# LCR.net
KiCad netlist of a schematic drawn in EAGLE
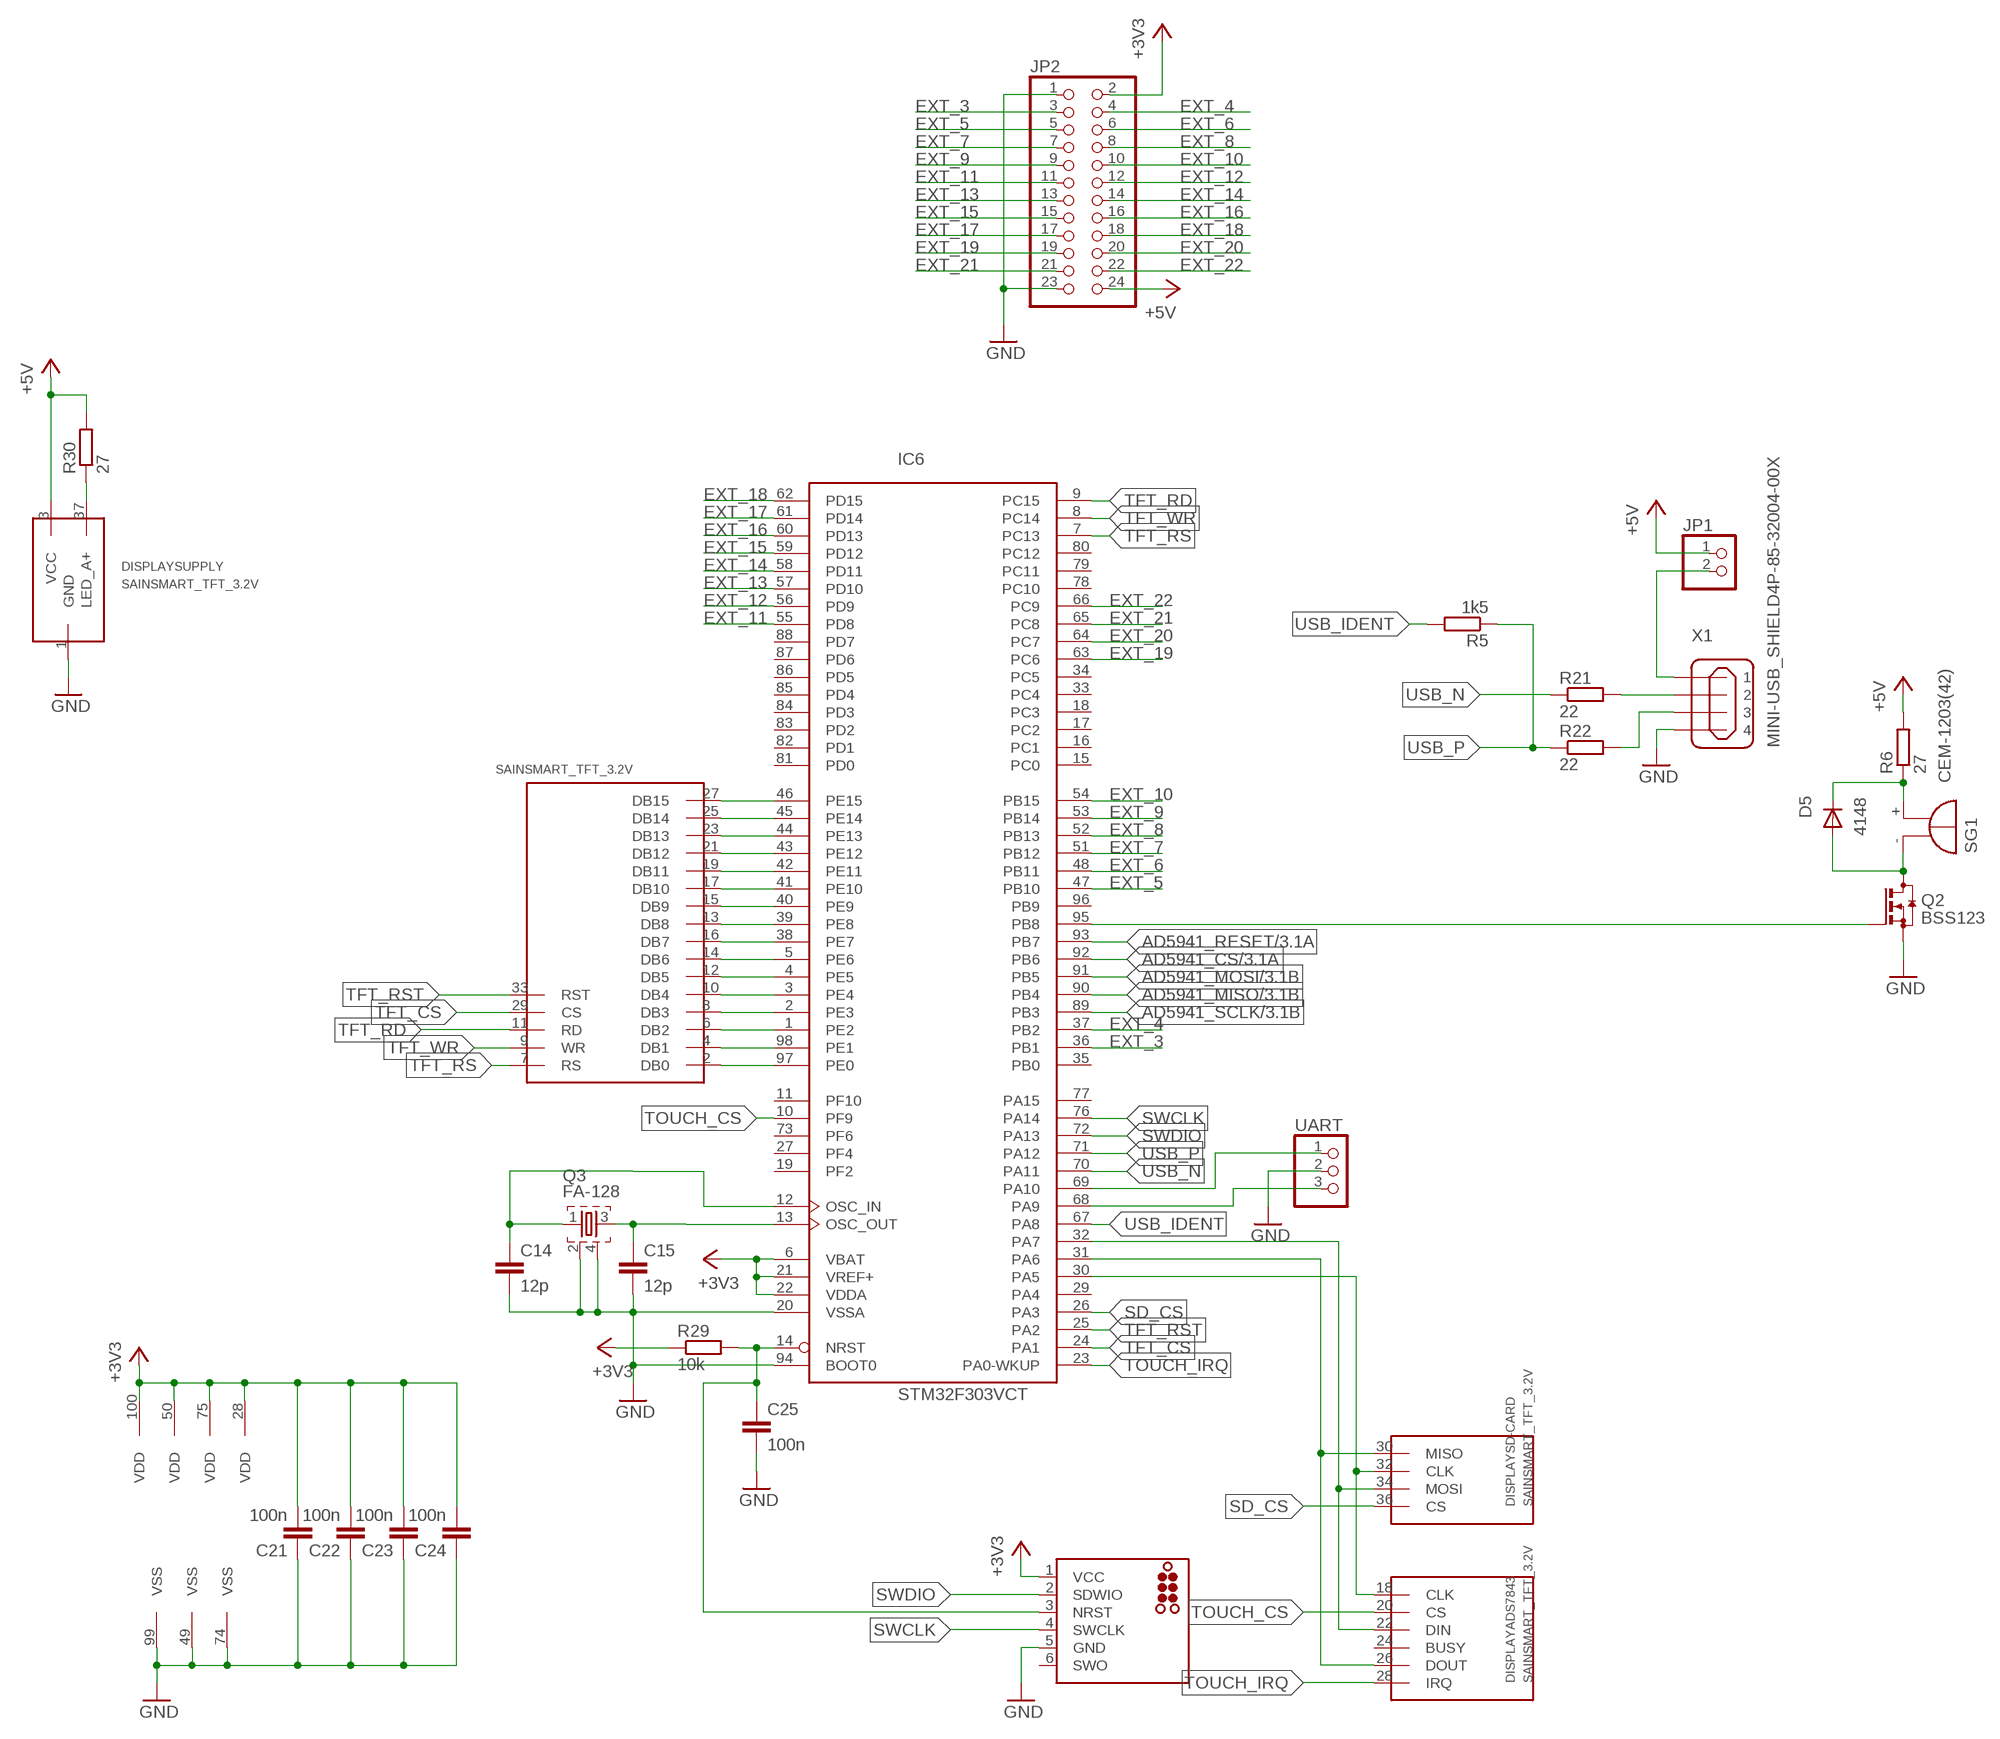
[diagram p0: schematic, sheet 1]
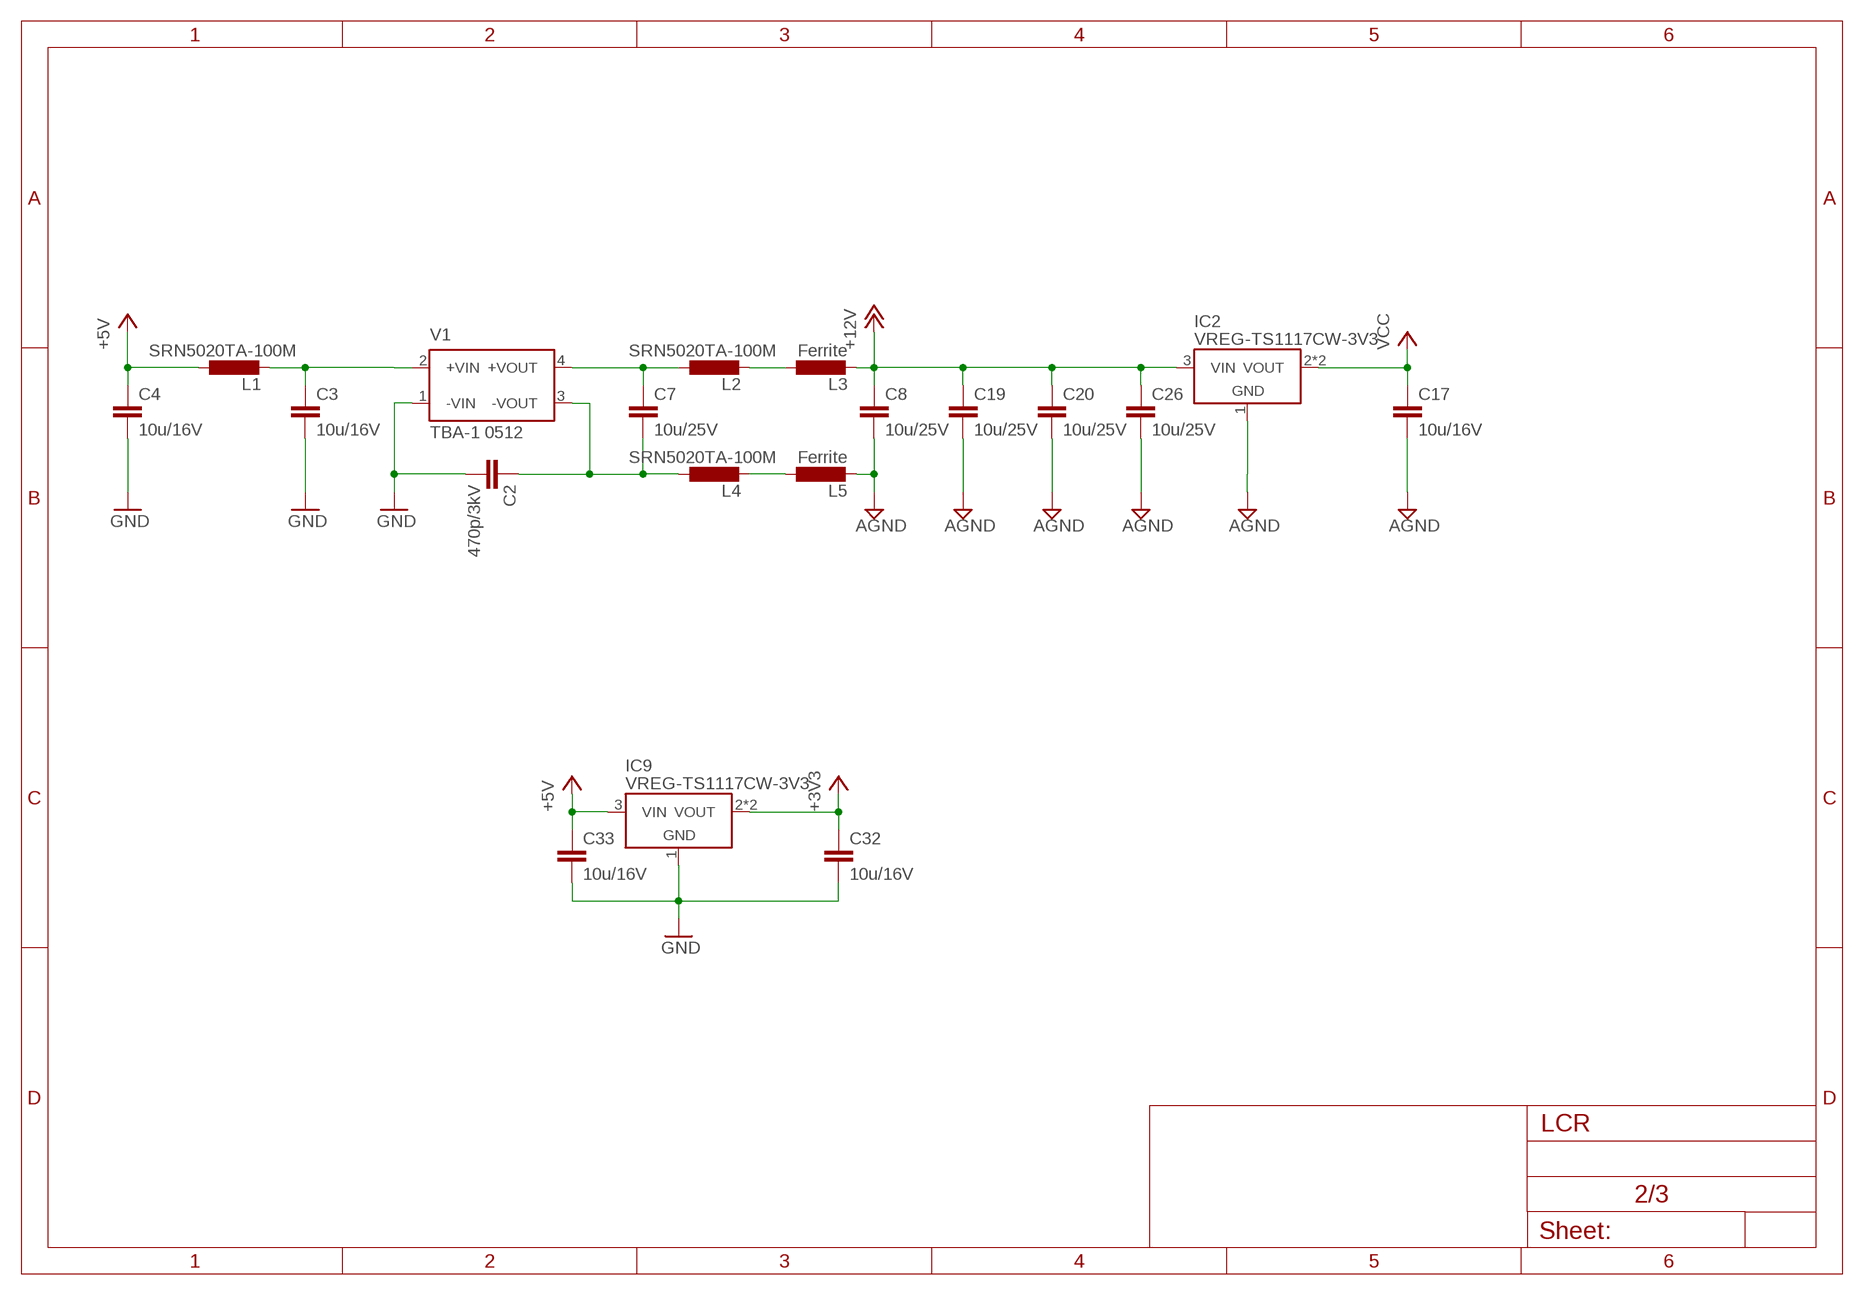
[diagram p1: schematic, sheet 2]
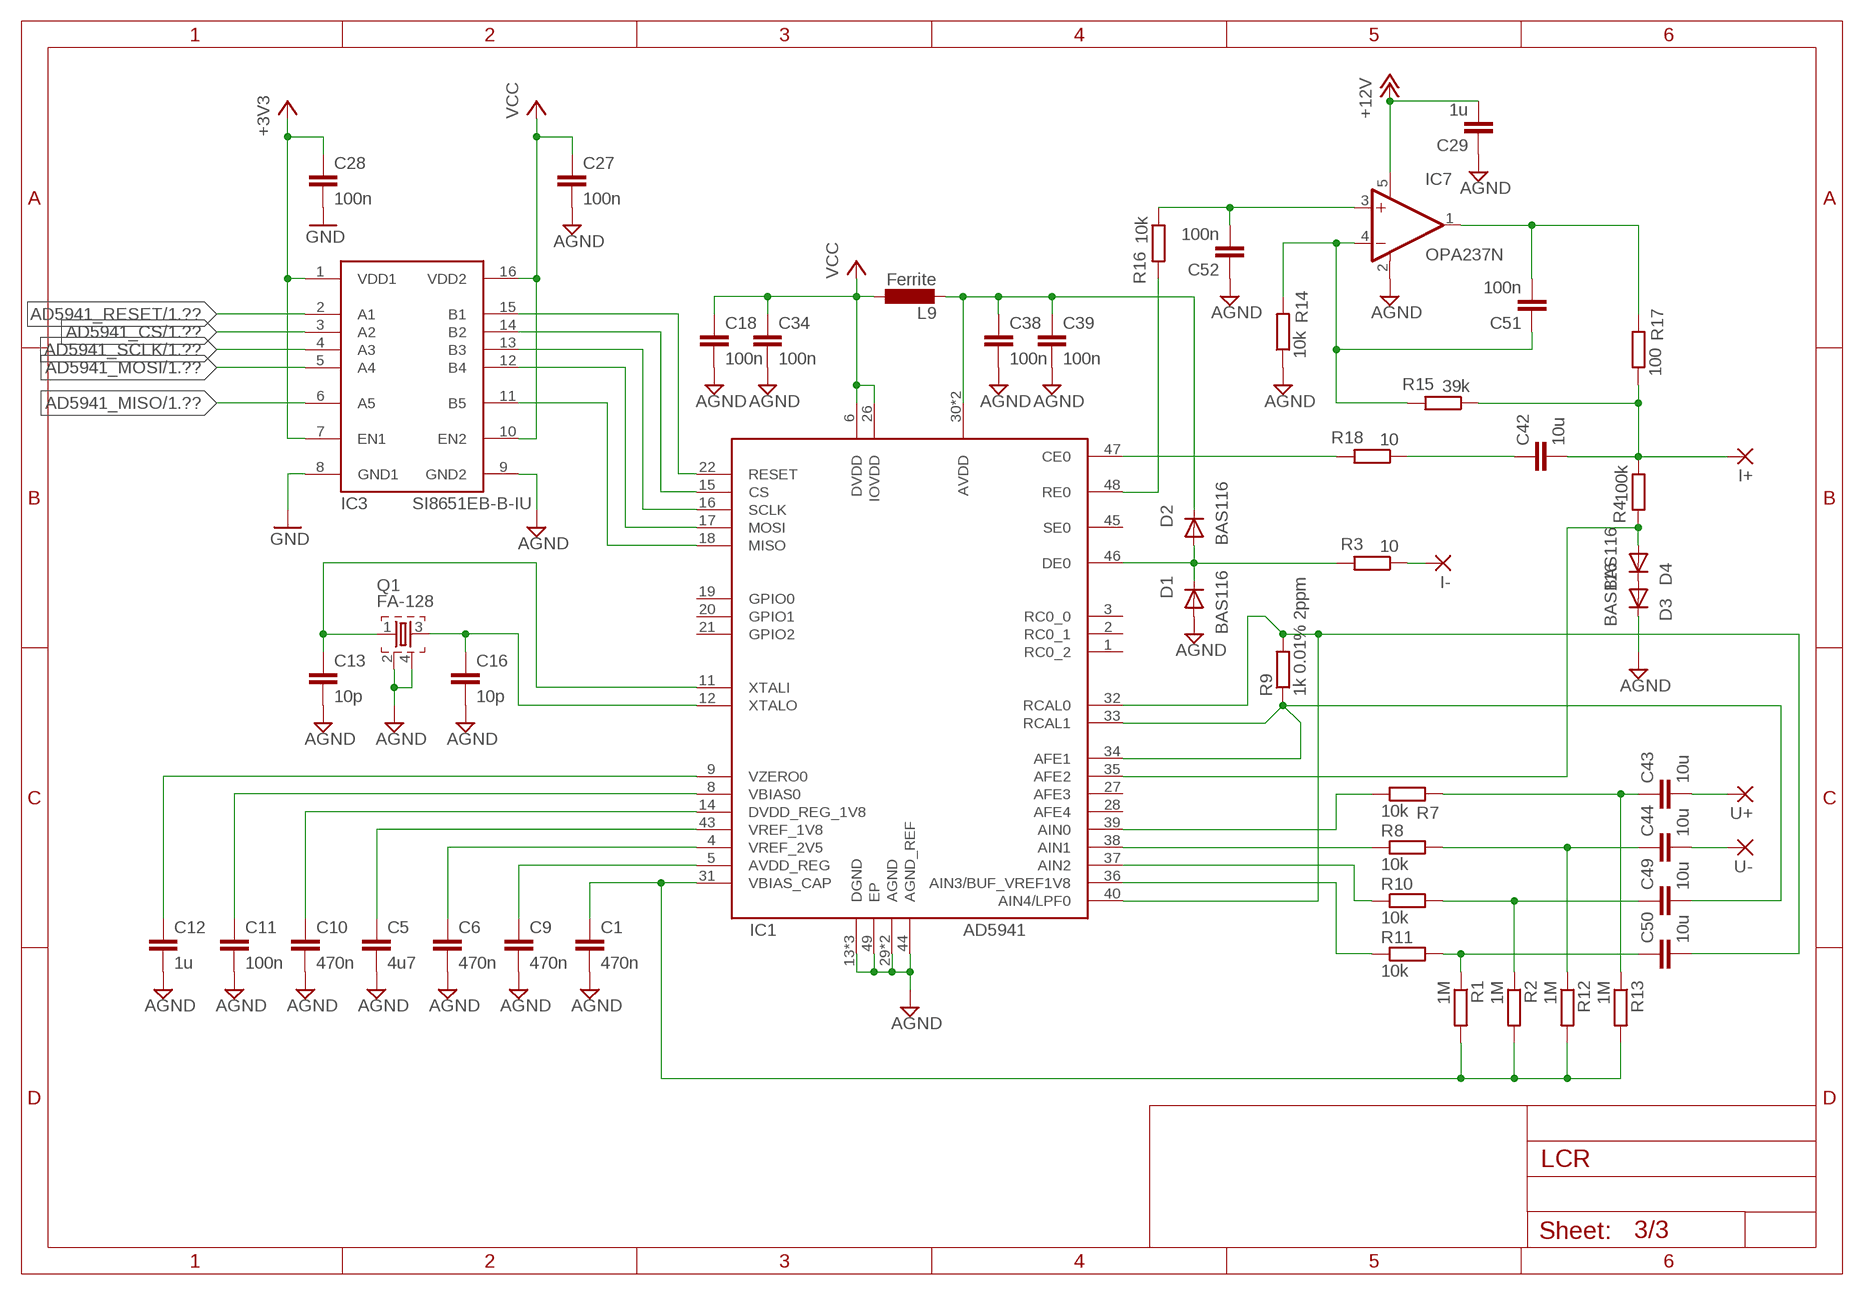
[diagram p2: schematic, sheet 3]

(export (version "E")
  (design (tool "Eeschema 10.0.6"))
  (components
    (comp (ref "C2")
      (value "470p/3kV")
      (footprint "eagle-import:C1812")
      (libsource (lib "eagle-import") (part "resistor_C-EUC1812"))
    )
    (comp (ref "C3")
      (value "10u/16V")
      (footprint "eagle-import:C1206K")
      (libsource (lib "eagle-import") (part "C-EUC1206K"))
    )
    (comp (ref "C4")
      (value "10u/16V")
      (footprint "eagle-import:C1206K")
      (libsource (lib "eagle-import") (part "C-EUC1206K"))
    )
    (comp (ref "C7")
      (value "10u/25V")
      (footprint "eagle-import:C1206K")
      (libsource (lib "eagle-import") (part "C-EUC1206K"))
    )
    (comp (ref "C8")
      (value "10u/25V")
      (footprint "eagle-import:C1206K")
      (libsource (lib "eagle-import") (part "C-EUC1206K"))
    )
    (comp (ref "C17")
      (value "10u/16V")
      (footprint "eagle-import:C1206K")
      (libsource (lib "eagle-import") (part "C-EUC1206K"))
    )
    (comp (ref "C19")
      (value "10u/25V")
      (footprint "eagle-import:C1206K")
      (libsource (lib "eagle-import") (part "C-EUC1206K"))
    )
    (comp (ref "C20")
      (value "10u/25V")
      (footprint "eagle-import:C1206K")
      (libsource (lib "eagle-import") (part "C-EUC1206K"))
    )
    (comp (ref "C26")
      (value "10u/25V")
      (footprint "eagle-import:C1206K")
      (libsource (lib "eagle-import") (part "C-EUC1206K"))
    )
    (comp (ref "C32")
      (value "10u/16V")
      (footprint "eagle-import:C1206K")
      (libsource (lib "eagle-import") (part "C-EUC1206K"))
    )
    (comp (ref "C33")
      (value "10u/16V")
      (footprint "eagle-import:C1206K")
      (libsource (lib "eagle-import") (part "C-EUC1206K"))
    )
    (comp (ref "IC2")
      (value "VREG-TS1117CW-3V3")
      (footprint "eagle-import:SOT223")
      (libsource (lib "eagle-import") (part "VREG-TS1117CW-3V3"))
    )
    (comp (ref "IC9")
      (value "VREG-TS1117CW-3V3")
      (footprint "eagle-import:SOT223")
      (libsource (lib "eagle-import") (part "VREG-TS1117CW-3V3"))
    )
    (comp (ref "L1")
      (value "SRN5020TA-100M")
      (footprint "eagle-import:SRN5040")
      (libsource (lib "eagle-import") (part "SRN5040"))
    )
    (comp (ref "L2")
      (value "SRN5020TA-100M")
      (footprint "eagle-import:SRN5040")
      (libsource (lib "eagle-import") (part "SRN5040"))
    )
    (comp (ref "L3")
      (value "Ferrite")
      (footprint "eagle-import:R0603")
      (libsource (lib "eagle-import") (part "INDUCTOR0603"))
    )
    (comp (ref "L4")
      (value "SRN5020TA-100M")
      (footprint "eagle-import:SRN5040")
      (libsource (lib "eagle-import") (part "SRN5040"))
    )
    (comp (ref "L5")
      (value "Ferrite")
      (footprint "eagle-import:R0603")
      (libsource (lib "eagle-import") (part "INDUCTOR0603"))
    )
    (comp (ref "V1")
      (value "TBA-1 0512")
      (footprint "eagle-import:TME")
      (fields (field (name "MPN") "TME 0505S"))
      (libsource (lib "eagle-import") (part "TME?0505S"))
    )
    (comp (ref "C1")
      (value "470n")
      (footprint "eagle-import:C0603K")
      (libsource (lib "eagle-import") (part "C-EUC0603K"))
    )
    (comp (ref "C5")
      (value "4u7")
      (footprint "eagle-import:C0603K")
      (libsource (lib "eagle-import") (part "C-EUC0603K"))
    )
    (comp (ref "C6")
      (value "470n")
      (footprint "eagle-import:C0603K")
      (libsource (lib "eagle-import") (part "C-EUC0603K"))
    )
    (comp (ref "C9")
      (value "470n")
      (footprint "eagle-import:C0603K")
      (libsource (lib "eagle-import") (part "C-EUC0603K"))
    )
    (comp (ref "C10")
      (value "470n")
      (footprint "eagle-import:C0603K")
      (libsource (lib "eagle-import") (part "C-EUC0603K"))
    )
    (comp (ref "C11")
      (value "100n")
      (footprint "eagle-import:C0603K")
      (libsource (lib "eagle-import") (part "C-EUC0603K"))
    )
    (comp (ref "C12")
      (value "1u")
      (footprint "eagle-import:C0603K")
      (libsource (lib "eagle-import") (part "C-EUC0603K"))
    )
    (comp (ref "C13")
      (value "10p")
      (footprint "eagle-import:C0603K")
      (libsource (lib "eagle-import") (part "C-EUC0603K"))
    )
    (comp (ref "C16")
      (value "10p")
      (footprint "eagle-import:C0603K")
      (libsource (lib "eagle-import") (part "C-EUC0603K"))
    )
    (comp (ref "C18")
      (value "100n")
      (footprint "eagle-import:C0603K")
      (libsource (lib "eagle-import") (part "C-EUC0603K"))
    )
    (comp (ref "C27")
      (value "100n")
      (footprint "eagle-import:C0603K")
      (libsource (lib "eagle-import") (part "C-EUC0603K"))
    )
    (comp (ref "C28")
      (value "100n")
      (footprint "eagle-import:C0603K")
      (libsource (lib "eagle-import") (part "C-EUC0603K"))
    )
    (comp (ref "C29")
      (value "1u")
      (footprint "eagle-import:C0603K")
      (libsource (lib "eagle-import") (part "C-EUC0603K"))
    )
    (comp (ref "C34")
      (value "100n")
      (footprint "eagle-import:C0603K")
      (libsource (lib "eagle-import") (part "C-EUC0603K"))
    )
    (comp (ref "C38")
      (value "100n")
      (footprint "eagle-import:C0603K")
      (libsource (lib "eagle-import") (part "C-EUC0603K"))
    )
    (comp (ref "C39")
      (value "100n")
      (footprint "eagle-import:C0603K")
      (libsource (lib "eagle-import") (part "C-EUC0603K"))
    )
    (comp (ref "C42")
      (value "10u")
      (footprint "eagle-import:C1206K")
      (libsource (lib "eagle-import") (part "resistor_C-EUC1206K"))
    )
    (comp (ref "C43")
      (value "10u")
      (footprint "eagle-import:C1206K")
      (libsource (lib "eagle-import") (part "resistor_C-EUC1206K"))
    )
    (comp (ref "C44")
      (value "10u")
      (footprint "eagle-import:C1206K")
      (libsource (lib "eagle-import") (part "resistor_C-EUC1206K"))
    )
    (comp (ref "C49")
      (value "10u")
      (footprint "eagle-import:C1206K")
      (libsource (lib "eagle-import") (part "resistor_C-EUC1206K"))
    )
    (comp (ref "C50")
      (value "10u")
      (footprint "eagle-import:C1206K")
      (libsource (lib "eagle-import") (part "resistor_C-EUC1206K"))
    )
    (comp (ref "C51")
      (value "100n")
      (footprint "eagle-import:C0603K")
      (libsource (lib "eagle-import") (part "C-EUC0603K"))
    )
    (comp (ref "C52")
      (value "100n")
      (footprint "eagle-import:C0603K")
      (libsource (lib "eagle-import") (part "C-EUC0603K"))
    )
    (comp (ref "D1")
      (value "BAS116")
      (footprint "eagle-import:SOD123")
      (libsource (lib "eagle-import") (part "DIODE-SOD123"))
    )
    (comp (ref "D2")
      (value "BAS116")
      (footprint "eagle-import:SOD123")
      (libsource (lib "eagle-import") (part "DIODE-SOD123"))
    )
    (comp (ref "D3")
      (value "BAS116")
      (footprint "eagle-import:SOD123")
      (libsource (lib "eagle-import") (part "DIODE-SOD123"))
    )
    (comp (ref "D4")
      (value "BAS116")
      (footprint "eagle-import:SOD123")
      (libsource (lib "eagle-import") (part "DIODE-SOD123"))
    )
    (comp (ref "I+")
      (value "2,54/1,1")
      (footprint "eagle-import:2,54_1,1")
      (libsource (lib "eagle-import") (part "2,54/1,1"))
    )
    (comp (ref "I-")
      (value "2,54/1,1")
      (footprint "eagle-import:2,54_1,1")
      (libsource (lib "eagle-import") (part "2,54/1,1"))
    )
    (comp (ref "IC1")
      (value "AD5941")
      (footprint "eagle-import:QFN50P700X700X80-49T510N")
      (libsource (lib "eagle-import") (part "AD5941"))
    )
    (comp (ref "IC3")
      (value "SI8651EB-B-IU")
      (footprint "eagle-import:SOP63P600X175-16N")
      (libsource (lib "eagle-import") (part "SI8651EB-B-IU"))
    )
    (comp (ref "IC7")
      (value "OPA237N")
      (footprint "eagle-import:SOT23-5")
      (fields (field (name "MF") "TEXAS INSTRUMENTS") (field (name "MPN") "OPA237NA/250"))
      (libsource (lib "eagle-import") (part "OPA237N"))
    )
    (comp (ref "L9")
      (value "Ferrite")
      (footprint "eagle-import:R0603")
      (libsource (lib "eagle-import") (part "INDUCTOR0603"))
    )
    (comp (ref "Q1")
      (value "FA-128")
      (footprint "eagle-import:FA-128")
      (libsource (lib "eagle-import") (part "FA-128"))
    )
    (comp (ref "R1")
      (value "1M")
      (footprint "eagle-import:R0603")
      (libsource (lib "eagle-import") (part "R-EU_R0603"))
    )
    (comp (ref "R2")
      (value "1M")
      (footprint "eagle-import:R0603")
      (libsource (lib "eagle-import") (part "R-EU_R0603"))
    )
    (comp (ref "R3")
      (value "10")
      (footprint "eagle-import:R0603")
      (libsource (lib "eagle-import") (part "R-EU_R0603"))
    )
    (comp (ref "R4")
      (value "100k")
      (footprint "eagle-import:R0603")
      (libsource (lib "eagle-import") (part "R-EU_R0603"))
    )
    (comp (ref "R7")
      (value "10k")
      (footprint "eagle-import:R0603")
      (libsource (lib "eagle-import") (part "R-EU_R0603"))
    )
    (comp (ref "R8")
      (value "10k")
      (footprint "eagle-import:R0603")
      (libsource (lib "eagle-import") (part "R-EU_R0603"))
    )
    (comp (ref "R9")
      (value "1k 0.01% 2ppm")
      (footprint "eagle-import:M0805")
      (libsource (lib "eagle-import") (part "resistor_R-EU_M0805"))
    )
    (comp (ref "R10")
      (value "10k")
      (footprint "eagle-import:R0603")
      (libsource (lib "eagle-import") (part "R-EU_R0603"))
    )
    (comp (ref "R11")
      (value "10k")
      (footprint "eagle-import:R0603")
      (libsource (lib "eagle-import") (part "R-EU_R0603"))
    )
    (comp (ref "R12")
      (value "1M")
      (footprint "eagle-import:R0603")
      (libsource (lib "eagle-import") (part "R-EU_R0603"))
    )
    (comp (ref "R13")
      (value "1M")
      (footprint "eagle-import:R0603")
      (libsource (lib "eagle-import") (part "R-EU_R0603"))
    )
    (comp (ref "R14")
      (value "10k")
      (footprint "eagle-import:R0603")
      (libsource (lib "eagle-import") (part "R-EU_R0603"))
    )
    (comp (ref "R15")
      (value "39k")
      (footprint "eagle-import:R0603")
      (libsource (lib "eagle-import") (part "R-EU_R0603"))
    )
    (comp (ref "R16")
      (value "10k")
      (footprint "eagle-import:R0603")
      (libsource (lib "eagle-import") (part "R-EU_R0603"))
    )
    (comp (ref "R17")
      (value "100")
      (footprint "eagle-import:R0603")
      (libsource (lib "eagle-import") (part "R-EU_R0603"))
    )
    (comp (ref "R18")
      (value "10")
      (footprint "eagle-import:R0603")
      (libsource (lib "eagle-import") (part "R-EU_R0603"))
    )
    (comp (ref "U+")
      (value "2,54/1,1")
      (footprint "eagle-import:2,54_1,1")
      (libsource (lib "eagle-import") (part "2,54/1,1"))
    )
    (comp (ref "U-")
      (value "2,54/1,1")
      (footprint "eagle-import:2,54_1,1")
      (libsource (lib "eagle-import") (part "2,54/1,1"))
    )
    (comp (ref "C14")
      (value "12p")
      (footprint "eagle-import:C0603K")
      (libsource (lib "eagle-import") (part "C-EUC0603K"))
    )
    (comp (ref "C15")
      (value "12p")
      (footprint "eagle-import:C0603K")
      (libsource (lib "eagle-import") (part "C-EUC0603K"))
    )
    (comp (ref "C21")
      (value "100n")
      (footprint "eagle-import:C0603K")
      (libsource (lib "eagle-import") (part "C-EUC0603K"))
    )
    (comp (ref "C22")
      (value "100n")
      (footprint "eagle-import:C0603K")
      (libsource (lib "eagle-import") (part "C-EUC0603K"))
    )
    (comp (ref "C23")
      (value "100n")
      (footprint "eagle-import:C0603K")
      (libsource (lib "eagle-import") (part "C-EUC0603K"))
    )
    (comp (ref "C24")
      (value "100n")
      (footprint "eagle-import:C0603K")
      (libsource (lib "eagle-import") (part "C-EUC0603K"))
    )
    (comp (ref "C25")
      (value "100n")
      (footprint "eagle-import:C0603K")
      (libsource (lib "eagle-import") (part "C-EUC0603K"))
    )
    (comp (ref "D5")
      (value "4148")
      (footprint "eagle-import:SOD123")
      (libsource (lib "eagle-import") (part "DIODE-SOD123"))
    )
    (comp (ref "DISPLAY")
      (value "SAINSMART_TFT_3.2V")
      (footprint "eagle-import:SAINSMART_ANGLED")
      (libsource (lib "eagle-import") (part "SAINSMART_TFT_3.2V"))
    )
    (comp (ref "IC6")
      (value "STM32F303VCT")
      (footprint "eagle-import:LQFP100")
      (libsource (lib "eagle-import") (part "STM32F303VTC"))
    )
    (comp (ref "J1")
      (value "TC2030-MCP")
      (footprint "eagle-import:TC2030-MCP")
      (libsource (lib "eagle-import") (part "TC2030-MCP"))
    )
    (comp (ref "JP1")
      (value "PINHD-1X2")
      (footprint "eagle-import:1X02")
      (libsource (lib "eagle-import") (part "PINHD-1X2"))
    )
    (comp (ref "JP2")
      (value "PINHD-2X12")
      (footprint "eagle-import:2X12")
      (libsource (lib "eagle-import") (part "PINHD-2X12"))
    )
    (comp (ref "Q2")
      (value "BSS123")
      (footprint "eagle-import:SOT23")
      (libsource (lib "eagle-import") (part "BSS123"))
    )
    (comp (ref "Q3")
      (value "FA-128")
      (footprint "eagle-import:FA-128")
      (libsource (lib "eagle-import") (part "FA-128"))
    )
    (comp (ref "R5")
      (value "1k5")
      (footprint "eagle-import:R0603")
      (libsource (lib "eagle-import") (part "resistor_R-EU_R0603"))
    )
    (comp (ref "R6")
      (value "27")
      (footprint "eagle-import:R1206")
      (libsource (lib "eagle-import") (part "resistor_R-EU_R1206"))
    )
    (comp (ref "R21")
      (value "22")
      (footprint "eagle-import:R0603")
      (libsource (lib "eagle-import") (part "resistor_R-EU_R0603"))
    )
    (comp (ref "R22")
      (value "22")
      (footprint "eagle-import:R0603")
      (libsource (lib "eagle-import") (part "resistor_R-EU_R0603"))
    )
    (comp (ref "R29")
      (value "10k")
      (footprint "eagle-import:R0603")
      (libsource (lib "eagle-import") (part "resistor_R-EU_R0603"))
    )
    (comp (ref "R30")
      (value "27")
      (footprint "eagle-import:R1206")
      (libsource (lib "eagle-import") (part "resistor_R-EU_R1206"))
    )
    (comp (ref "SG1")
      (value "CEM-1203(42)")
      (footprint "eagle-import:F_QMBIII")
      (libsource (lib "eagle-import") (part "F/QMBIII"))
    )
    (comp (ref "UART")
      (value "PINHD-1X3")
      (footprint "eagle-import:1X03")
      (libsource (lib "eagle-import") (part "PINHD-1X3"))
    )
    (comp (ref "X1")
      (value "MINI-USB_SHIELD4P-85-32004-00X")
      (footprint "eagle-import:85-32004-00X")
      (libsource (lib "eagle-import") (part "MINI-USB_SHIELD4P-85-32004-00X"))
    )
  )
  (nets
    (net (code "1") (name "+3V3") (class "Default")
      (node (ref "C21") (pin "2") (pinfunction "2_2") (pintype "passive"))
      (node (ref "C22") (pin "2") (pinfunction "2_2") (pintype "passive"))
      (node (ref "C23") (pin "2") (pinfunction "2_2") (pintype "passive"))
      (node (ref "C24") (pin "2") (pinfunction "2_2") (pintype "passive"))
      (node (ref "C28") (pin "1") (pinfunction "1_1") (pintype "passive"))
      (node (ref "C32") (pin "1") (pinfunction "1_1") (pintype "passive"))
      (node (ref "IC3") (pin "1") (pinfunction "VDD1_1") (pintype "bidirectional"))
      (node (ref "IC3") (pin "7") (pinfunction "EN1_7") (pintype "bidirectional"))
      (node (ref "IC6") (pin "100") (pinfunction "VDD_100") (pintype "power_in"))
      (node (ref "IC6") (pin "21") (pinfunction "VREF+_21") (pintype "power_in"))
      (node (ref "IC6") (pin "22") (pinfunction "VDDA_22") (pintype "power_in"))
      (node (ref "IC6") (pin "28") (pinfunction "VDD_28") (pintype "power_in"))
      (node (ref "IC6") (pin "50") (pinfunction "VDD_50") (pintype "power_in"))
      (node (ref "IC6") (pin "6") (pinfunction "VBAT_6") (pintype "power_in"))
      (node (ref "IC6") (pin "75") (pinfunction "VDD_75") (pintype "power_in"))
      (node (ref "IC9") (pin "2") (pinfunction "VOUT_2") (pintype "power_in"))
      (node (ref "IC9") (pin "4") (pinfunction "VOUT_4") (pintype "power_in"))
      (node (ref "J1") (pin "1") (pinfunction "VCC_1") (pintype "passive"))
      (node (ref "JP2") (pin "2") (pinfunction "2_2") (pintype "passive"))
      (node (ref "R29") (pin "1") (pinfunction "1_1") (pintype "passive"))
    )
    (net (code "2") (name "+5V") (class "Default")
      (node (ref "C33") (pin "1") (pinfunction "1_1") (pintype "passive"))
      (node (ref "C4") (pin "1") (pinfunction "1_1") (pintype "passive"))
      (node (ref "DISPLAY") (pin "3") (pinfunction "VCC_3") (pintype "bidirectional"))
      (node (ref "IC9") (pin "3") (pinfunction "VIN_3") (pintype "power_in"))
      (node (ref "JP1") (pin "1") (pinfunction "1_1") (pintype "passive"))
      (node (ref "JP2") (pin "24") (pinfunction "24_24") (pintype "passive"))
      (node (ref "L1") (pin "P$1") (pinfunction "1_P$1") (pintype "passive"))
      (node (ref "R30") (pin "2") (pinfunction "2_2") (pintype "passive"))
      (node (ref "R6") (pin "2") (pinfunction "2_2") (pintype "passive"))
    )
    (net (code "3") (name "+12V") (class "Default")
      (node (ref "C19") (pin "1") (pinfunction "1_1") (pintype "passive"))
      (node (ref "C20") (pin "1") (pinfunction "1_1") (pintype "passive"))
      (node (ref "C26") (pin "1") (pinfunction "1_1") (pintype "passive"))
      (node (ref "C29") (pin "2") (pinfunction "2_2") (pintype "passive"))
      (node (ref "C8") (pin "1") (pinfunction "1_1") (pintype "passive"))
      (node (ref "IC2") (pin "3") (pinfunction "VIN_3") (pintype "power_in"))
      (node (ref "IC7") (pin "5") (pinfunction "V+_5") (pintype "power_in"))
      (node (ref "L3") (pin "2") (pinfunction "2_2") (pintype "passive"))
    )
    (net (code "4") (name "AD5941_CS") (class "Default")
      (node (ref "IC3") (pin "3") (pinfunction "A2_3") (pintype "bidirectional"))
      (node (ref "IC6") (pin "92") (pinfunction "PB6_92") (pintype "bidirectional"))
    )
    (net (code "5") (name "AD5941_MISO") (class "Default")
      (node (ref "IC3") (pin "6") (pinfunction "A5_6") (pintype "bidirectional"))
      (node (ref "IC6") (pin "90") (pinfunction "PB4_90") (pintype "bidirectional"))
    )
    (net (code "6") (name "AD5941_MOSI") (class "Default")
      (node (ref "IC3") (pin "5") (pinfunction "A4_5") (pintype "bidirectional"))
      (node (ref "IC6") (pin "91") (pinfunction "PB5_91") (pintype "bidirectional"))
    )
    (net (code "7") (name "AD5941_RESET") (class "Default")
      (node (ref "IC3") (pin "2") (pinfunction "A1_2") (pintype "bidirectional"))
      (node (ref "IC6") (pin "93") (pinfunction "PB7_93") (pintype "bidirectional"))
    )
    (net (code "8") (name "AD5941_SCLK") (class "Default")
      (node (ref "IC3") (pin "4") (pinfunction "A3_4") (pintype "bidirectional"))
      (node (ref "IC6") (pin "89") (pinfunction "PB3_89") (pintype "bidirectional"))
    )
    (net (code "9") (name "AGND") (class "Default")
      (node (ref "C1") (pin "2") (pinfunction "2_2") (pintype "passive"))
      (node (ref "C10") (pin "2") (pinfunction "2_2") (pintype "passive"))
      (node (ref "C11") (pin "2") (pinfunction "2_2") (pintype "passive"))
      (node (ref "C12") (pin "2") (pinfunction "2_2") (pintype "passive"))
      (node (ref "C13") (pin "2") (pinfunction "2_2") (pintype "passive"))
      (node (ref "C16") (pin "2") (pinfunction "2_2") (pintype "passive"))
      (node (ref "C17") (pin "2") (pinfunction "2_2") (pintype "passive"))
      (node (ref "C18") (pin "2") (pinfunction "2_2") (pintype "passive"))
      (node (ref "C19") (pin "2") (pinfunction "2_2") (pintype "passive"))
      (node (ref "C20") (pin "2") (pinfunction "2_2") (pintype "passive"))
      (node (ref "C26") (pin "2") (pinfunction "2_2") (pintype "passive"))
      (node (ref "C27") (pin "2") (pinfunction "2_2") (pintype "passive"))
      (node (ref "C29") (pin "1") (pinfunction "1_1") (pintype "passive"))
      (node (ref "C34") (pin "2") (pinfunction "2_2") (pintype "passive"))
      (node (ref "C38") (pin "2") (pinfunction "2_2") (pintype "passive"))
      (node (ref "C39") (pin "2") (pinfunction "2_2") (pintype "passive"))
      (node (ref "C5") (pin "2") (pinfunction "2_2") (pintype "passive"))
      (node (ref "C52") (pin "1") (pinfunction "1_1") (pintype "passive"))
      (node (ref "C6") (pin "2") (pinfunction "2_2") (pintype "passive"))
      (node (ref "C8") (pin "2") (pinfunction "2_2") (pintype "passive"))
      (node (ref "C9") (pin "2") (pinfunction "2_2") (pintype "passive"))
      (node (ref "D1") (pin "A") (pinfunction "A_A") (pintype "passive"))
      (node (ref "D3") (pin "C") (pinfunction "C_C") (pintype "passive"))
      (node (ref "IC1") (pin "13") (pinfunction "DGND_13") (pintype "bidirectional"))
      (node (ref "IC1") (pin "23") (pinfunction "DGND_23") (pintype "bidirectional"))
      (node (ref "IC1") (pin "25") (pinfunction "DGND_25") (pintype "bidirectional"))
      (node (ref "IC1") (pin "29") (pinfunction "AGND_29") (pintype "bidirectional"))
      (node (ref "IC1") (pin "42") (pinfunction "AGND_42") (pintype "bidirectional"))
      (node (ref "IC1") (pin "44") (pinfunction "AGND_REF_44") (pintype "bidirectional"))
      (node (ref "IC1") (pin "49") (pinfunction "EP_49") (pintype "bidirectional"))
      (node (ref "IC2") (pin "1") (pinfunction "GND_1") (pintype "power_in"))
      (node (ref "IC3") (pin "9") (pinfunction "GND2_9") (pintype "bidirectional"))
      (node (ref "IC7") (pin "2") (pinfunction "V-_2") (pintype "power_in"))
      (node (ref "L5") (pin "2") (pinfunction "2_2") (pintype "passive"))
      (node (ref "Q1") (pin "2") (pinfunction "2_2") (pintype "passive"))
      (node (ref "Q1") (pin "4") (pinfunction "4_4") (pintype "passive"))
      (node (ref "R14") (pin "1") (pinfunction "1_1") (pintype "passive"))
    )
    (net (code "10") (name "EXT_3") (class "Default")
      (node (ref "IC6") (pin "36") (pinfunction "PB1_36") (pintype "bidirectional"))
      (node (ref "JP2") (pin "3") (pinfunction "3_3") (pintype "passive"))
    )
    (net (code "11") (name "EXT_4") (class "Default")
      (node (ref "IC6") (pin "37") (pinfunction "PB2_37") (pintype "bidirectional"))
      (node (ref "JP2") (pin "4") (pinfunction "4_4") (pintype "passive"))
    )
    (net (code "12") (name "EXT_5") (class "Default")
      (node (ref "IC6") (pin "47") (pinfunction "PB10_47") (pintype "bidirectional"))
      (node (ref "JP2") (pin "5") (pinfunction "5_5") (pintype "passive"))
    )
    (net (code "13") (name "EXT_6") (class "Default")
      (node (ref "IC6") (pin "48") (pinfunction "PB11_48") (pintype "bidirectional"))
      (node (ref "JP2") (pin "6") (pinfunction "6_6") (pintype "passive"))
    )
    (net (code "14") (name "EXT_7") (class "Default")
      (node (ref "IC6") (pin "51") (pinfunction "PB12_51") (pintype "bidirectional"))
      (node (ref "JP2") (pin "7") (pinfunction "7_7") (pintype "passive"))
    )
    (net (code "15") (name "EXT_8") (class "Default")
      (node (ref "IC6") (pin "52") (pinfunction "PB13_52") (pintype "bidirectional"))
      (node (ref "JP2") (pin "8") (pinfunction "8_8") (pintype "passive"))
    )
    (net (code "16") (name "EXT_9") (class "Default")
      (node (ref "IC6") (pin "53") (pinfunction "PB14_53") (pintype "bidirectional"))
      (node (ref "JP2") (pin "9") (pinfunction "9_9") (pintype "passive"))
    )
    (net (code "17") (name "EXT_10") (class "Default")
      (node (ref "IC6") (pin "54") (pinfunction "PB15_54") (pintype "bidirectional"))
      (node (ref "JP2") (pin "10") (pinfunction "10_10") (pintype "passive"))
    )
    (net (code "18") (name "EXT_11") (class "Default")
      (node (ref "IC6") (pin "55") (pinfunction "PD8_55") (pintype "bidirectional"))
      (node (ref "JP2") (pin "11") (pinfunction "11_11") (pintype "passive"))
    )
    (net (code "19") (name "EXT_12") (class "Default")
      (node (ref "IC6") (pin "56") (pinfunction "PD9_56") (pintype "bidirectional"))
      (node (ref "JP2") (pin "12") (pinfunction "12_12") (pintype "passive"))
    )
    (net (code "20") (name "EXT_13") (class "Default")
      (node (ref "IC6") (pin "57") (pinfunction "PD10_57") (pintype "bidirectional"))
      (node (ref "JP2") (pin "13") (pinfunction "13_13") (pintype "passive"))
    )
    (net (code "21") (name "EXT_14") (class "Default")
      (node (ref "IC6") (pin "58") (pinfunction "PD11_58") (pintype "bidirectional"))
      (node (ref "JP2") (pin "14") (pinfunction "14_14") (pintype "passive"))
    )
    (net (code "22") (name "EXT_15") (class "Default")
      (node (ref "IC6") (pin "59") (pinfunction "PD12_59") (pintype "bidirectional"))
      (node (ref "JP2") (pin "15") (pinfunction "15_15") (pintype "passive"))
    )
    (net (code "23") (name "EXT_16") (class "Default")
      (node (ref "IC6") (pin "60") (pinfunction "PD13_60") (pintype "bidirectional"))
      (node (ref "JP2") (pin "16") (pinfunction "16_16") (pintype "passive"))
    )
    (net (code "24") (name "EXT_17") (class "Default")
      (node (ref "IC6") (pin "61") (pinfunction "PD14_61") (pintype "bidirectional"))
      (node (ref "JP2") (pin "17") (pinfunction "17_17") (pintype "passive"))
    )
    (net (code "25") (name "EXT_18") (class "Default")
      (node (ref "IC6") (pin "62") (pinfunction "PD15_62") (pintype "bidirectional"))
      (node (ref "JP2") (pin "18") (pinfunction "18_18") (pintype "passive"))
    )
    (net (code "26") (name "EXT_19") (class "Default")
      (node (ref "IC6") (pin "63") (pinfunction "PC6_63") (pintype "bidirectional"))
      (node (ref "JP2") (pin "19") (pinfunction "19_19") (pintype "passive"))
    )
    (net (code "27") (name "EXT_20") (class "Default")
      (node (ref "IC6") (pin "64") (pinfunction "PC7_64") (pintype "bidirectional"))
      (node (ref "JP2") (pin "20") (pinfunction "20_20") (pintype "passive"))
    )
    (net (code "28") (name "EXT_21") (class "Default")
      (node (ref "IC6") (pin "65") (pinfunction "PC8_65") (pintype "bidirectional"))
      (node (ref "JP2") (pin "21") (pinfunction "21_21") (pintype "passive"))
    )
    (net (code "29") (name "EXT_22") (class "Default")
      (node (ref "IC6") (pin "66") (pinfunction "PC9_66") (pintype "bidirectional"))
      (node (ref "JP2") (pin "22") (pinfunction "22_22") (pintype "passive"))
    )
    (net (code "30") (name "GND") (class "Default")
      (node (ref "C14") (pin "2") (pinfunction "2_2") (pintype "passive"))
      (node (ref "C15") (pin "2") (pinfunction "2_2") (pintype "passive"))
      (node (ref "C2") (pin "2") (pinfunction "2_2") (pintype "passive"))
      (node (ref "C21") (pin "1") (pinfunction "1_1") (pintype "passive"))
      (node (ref "C22") (pin "1") (pinfunction "1_1") (pintype "passive"))
      (node (ref "C23") (pin "1") (pinfunction "1_1") (pintype "passive"))
      (node (ref "C24") (pin "1") (pinfunction "1_1") (pintype "passive"))
      (node (ref "C25") (pin "2") (pinfunction "2_2") (pintype "passive"))
      (node (ref "C28") (pin "2") (pinfunction "2_2") (pintype "passive"))
      (node (ref "C3") (pin "2") (pinfunction "2_2") (pintype "passive"))
      (node (ref "C32") (pin "2") (pinfunction "2_2") (pintype "passive"))
      (node (ref "C33") (pin "2") (pinfunction "2_2") (pintype "passive"))
      (node (ref "C4") (pin "2") (pinfunction "2_2") (pintype "passive"))
      (node (ref "DISPLAY") (pin "1") (pinfunction "GND_1") (pintype "bidirectional"))
      (node (ref "IC3") (pin "8") (pinfunction "GND1_8") (pintype "bidirectional"))
      (node (ref "IC6") (pin "20") (pinfunction "VSSA_20") (pintype "power_in"))
      (node (ref "IC6") (pin "49") (pinfunction "VSS_49") (pintype "power_in"))
      (node (ref "IC6") (pin "74") (pinfunction "VSS_74") (pintype "power_in"))
      (node (ref "IC6") (pin "94") (pinfunction "BOOT0_94") (pintype "input"))
      (node (ref "IC6") (pin "99") (pinfunction "VSS_99") (pintype "power_in"))
      (node (ref "IC9") (pin "1") (pinfunction "GND_1") (pintype "power_in"))
      (node (ref "J1") (pin "5") (pinfunction "GND_5") (pintype "output"))
      (node (ref "JP2") (pin "1") (pinfunction "1_1") (pintype "passive"))
      (node (ref "JP2") (pin "23") (pinfunction "23_23") (pintype "passive"))
      (node (ref "Q2") (pin "2") (pinfunction "S_2") (pintype "passive"))
      (node (ref "Q3") (pin "2") (pinfunction "2_2") (pintype "passive"))
      (node (ref "Q3") (pin "4") (pinfunction "4_4") (pintype "passive"))
      (node (ref "UART") (pin "2") (pinfunction "2_2") (pintype "passive"))
      (node (ref "V1") (pin "1") (pinfunction "-VIN_1") (pintype "passive"))
      (node (ref "X1") (pin "4") (pinfunction "4_4") (pintype "passive"))
    )
    (net (code "31") (name "Net-(C38-Pad1)") (class "Default")
      (node (ref "C38") (pin "1") (pinfunction "1_1") (pintype "passive"))
      (node (ref "C39") (pin "1") (pinfunction "1_1") (pintype "passive"))
      (node (ref "D2") (pin "C") (pinfunction "C_C") (pintype "passive"))
      (node (ref "IC1") (pin "30") (pinfunction "AVDD_30") (pintype "bidirectional"))
      (node (ref "IC1") (pin "41") (pinfunction "AVDD_41") (pintype "bidirectional"))
      (node (ref "L9") (pin "2") (pinfunction "2_2") (pintype "passive"))
    )
    (net (code "32") (name "Net-(C42-Pad1)") (class "Default")
      (node (ref "C42") (pin "1") (pinfunction "1_1") (pintype "passive"))
      (node (ref "R18") (pin "1") (pinfunction "1_1") (pintype "passive"))
    )
    (net (code "33") (name "Net-(C43-Pad1)") (class "Default")
      (node (ref "C43") (pin "1") (pinfunction "1_1") (pintype "passive"))
      (node (ref "R13") (pin "1") (pinfunction "1_1") (pintype "passive"))
      (node (ref "R7") (pin "2") (pinfunction "2_2") (pintype "passive"))
    )
    (net (code "34") (name "Net-(C44-Pad1)") (class "Default")
      (node (ref "C44") (pin "1") (pinfunction "1_1") (pintype "passive"))
      (node (ref "R12") (pin "1") (pinfunction "1_1") (pintype "passive"))
      (node (ref "R8") (pin "2") (pinfunction "2_2") (pintype "passive"))
    )
    (net (code "35") (name "Net-(C49-Pad1)") (class "Default")
      (node (ref "C49") (pin "1") (pinfunction "1_1") (pintype "passive"))
      (node (ref "R10") (pin "2") (pinfunction "2_2") (pintype "passive"))
      (node (ref "R2") (pin "1") (pinfunction "1_1") (pintype "passive"))
    )
    (net (code "36") (name "Net-(C50-Pad1)") (class "Default")
      (node (ref "C50") (pin "1") (pinfunction "1_1") (pintype "passive"))
      (node (ref "R1") (pin "1") (pinfunction "1_1") (pintype "passive"))
      (node (ref "R11") (pin "2") (pinfunction "2_2") (pintype "passive"))
    )
    (net (code "37") (name "Net-(D3-PadA)") (class "Default")
      (node (ref "D3") (pin "A") (pinfunction "A_A") (pintype "passive"))
      (node (ref "D4") (pin "C") (pinfunction "C_C") (pintype "passive"))
    )
    (net (code "38") (name "Net-(DISPLAYA-CLK)") (class "Default")
      (node (ref "DISPLAY") (pin "18") (pinfunction "CLK_18") (pintype "bidirectional"))
      (node (ref "DISPLAY") (pin "32") (pinfunction "CLK_32") (pintype "bidirectional"))
      (node (ref "IC6") (pin "30") (pinfunction "PA5_30") (pintype "bidirectional"))
    )
    (net (code "39") (name "Net-(DISPLAYA-DIN)") (class "Default")
      (node (ref "DISPLAY") (pin "22") (pinfunction "DIN_22") (pintype "bidirectional"))
      (node (ref "DISPLAY") (pin "34") (pinfunction "MOSI_34") (pintype "bidirectional"))
      (node (ref "IC6") (pin "32") (pinfunction "PA7_32") (pintype "bidirectional"))
    )
    (net (code "40") (name "Net-(DISPLAYA-DOUT)") (class "Default")
      (node (ref "DISPLAY") (pin "26") (pinfunction "DOUT_26") (pintype "bidirectional"))
      (node (ref "DISPLAY") (pin "30") (pinfunction "MISO_30") (pintype "bidirectional"))
      (node (ref "IC6") (pin "31") (pinfunction "PA6_31") (pintype "bidirectional"))
    )
    (net (code "41") (name "Net-(DISPLAYC-DB0)") (class "Default")
      (node (ref "DISPLAY") (pin "2") (pinfunction "DB0_2") (pintype "bidirectional"))
      (node (ref "IC6") (pin "97") (pinfunction "PE0_97") (pintype "bidirectional"))
    )
    (net (code "42") (name "Net-(DISPLAYC-DB1)") (class "Default")
      (node (ref "DISPLAY") (pin "4") (pinfunction "DB1_4") (pintype "bidirectional"))
      (node (ref "IC6") (pin "98") (pinfunction "PE1_98") (pintype "bidirectional"))
    )
    (net (code "43") (name "Net-(DISPLAYC-DB2)") (class "Default")
      (node (ref "DISPLAY") (pin "6") (pinfunction "DB2_6") (pintype "bidirectional"))
      (node (ref "IC6") (pin "1") (pinfunction "PE2_1") (pintype "bidirectional"))
    )
    (net (code "44") (name "Net-(DISPLAYC-DB3)") (class "Default")
      (node (ref "DISPLAY") (pin "8") (pinfunction "DB3_8") (pintype "bidirectional"))
      (node (ref "IC6") (pin "2") (pinfunction "PE3_2") (pintype "bidirectional"))
    )
    (net (code "45") (name "Net-(DISPLAYC-DB4)") (class "Default")
      (node (ref "DISPLAY") (pin "10") (pinfunction "DB4_10") (pintype "bidirectional"))
      (node (ref "IC6") (pin "3") (pinfunction "PE4_3") (pintype "bidirectional"))
    )
    (net (code "46") (name "Net-(DISPLAYC-DB5)") (class "Default")
      (node (ref "DISPLAY") (pin "12") (pinfunction "DB5_12") (pintype "bidirectional"))
      (node (ref "IC6") (pin "4") (pinfunction "PE5_4") (pintype "bidirectional"))
    )
    (net (code "47") (name "Net-(DISPLAYC-DB6)") (class "Default")
      (node (ref "DISPLAY") (pin "14") (pinfunction "DB6_14") (pintype "bidirectional"))
      (node (ref "IC6") (pin "5") (pinfunction "PE6_5") (pintype "bidirectional"))
    )
    (net (code "48") (name "Net-(DISPLAYC-DB7)") (class "Default")
      (node (ref "DISPLAY") (pin "16") (pinfunction "DB7_16") (pintype "bidirectional"))
      (node (ref "IC6") (pin "38") (pinfunction "PE7_38") (pintype "bidirectional"))
    )
    (net (code "49") (name "Net-(DISPLAYC-DB8)") (class "Default")
      (node (ref "DISPLAY") (pin "13") (pinfunction "DB8_13") (pintype "bidirectional"))
      (node (ref "IC6") (pin "39") (pinfunction "PE8_39") (pintype "bidirectional"))
    )
    (net (code "50") (name "Net-(DISPLAYC-DB9)") (class "Default")
      (node (ref "DISPLAY") (pin "15") (pinfunction "DB9_15") (pintype "bidirectional"))
      (node (ref "IC6") (pin "40") (pinfunction "PE9_40") (pintype "bidirectional"))
    )
    (net (code "51") (name "Net-(DISPLAYC-DB10)") (class "Default")
      (node (ref "DISPLAY") (pin "17") (pinfunction "DB10_17") (pintype "bidirectional"))
      (node (ref "IC6") (pin "41") (pinfunction "PE10_41") (pintype "bidirectional"))
    )
    (net (code "52") (name "Net-(DISPLAYC-DB11)") (class "Default")
      (node (ref "DISPLAY") (pin "19") (pinfunction "DB11_19") (pintype "bidirectional"))
      (node (ref "IC6") (pin "42") (pinfunction "PE11_42") (pintype "bidirectional"))
    )
    (net (code "53") (name "Net-(DISPLAYC-DB12)") (class "Default")
      (node (ref "DISPLAY") (pin "21") (pinfunction "DB12_21") (pintype "bidirectional"))
      (node (ref "IC6") (pin "43") (pinfunction "PE12_43") (pintype "bidirectional"))
    )
    (net (code "54") (name "Net-(DISPLAYC-DB13)") (class "Default")
      (node (ref "DISPLAY") (pin "23") (pinfunction "DB13_23") (pintype "bidirectional"))
      (node (ref "IC6") (pin "44") (pinfunction "PE13_44") (pintype "bidirectional"))
    )
    (net (code "55") (name "Net-(DISPLAYC-DB14)") (class "Default")
      (node (ref "DISPLAY") (pin "25") (pinfunction "DB14_25") (pintype "bidirectional"))
      (node (ref "IC6") (pin "45") (pinfunction "PE14_45") (pintype "bidirectional"))
    )
    (net (code "56") (name "Net-(DISPLAYC-DB15)") (class "Default")
      (node (ref "DISPLAY") (pin "27") (pinfunction "DB15_27") (pintype "bidirectional"))
      (node (ref "IC6") (pin "46") (pinfunction "PE15_46") (pintype "bidirectional"))
    )
    (net (code "57") (name "Net-(DISPLAYD-LED_A+)") (class "Default")
      (node (ref "DISPLAY") (pin "37") (pinfunction "LED_A+_37") (pintype "bidirectional"))
      (node (ref "R30") (pin "1") (pinfunction "1_1") (pintype "passive"))
    )
    (net (code "58") (name "Net-(I+-P)") (class "Default")
      (node (ref "C42") (pin "2") (pinfunction "2_2") (pintype "passive"))
      (node (ref "I+") (pin "1") (pinfunction "P_1") (pintype "passive"))
      (node (ref "R15") (pin "1") (pinfunction "1_1") (pintype "passive"))
      (node (ref "R17") (pin "1") (pinfunction "1_1") (pintype "passive"))
      (node (ref "R4") (pin "1") (pinfunction "1_1") (pintype "passive"))
    )
    (net (code "59") (name "Net-(I--P)") (class "Default")
      (node (ref "I-") (pin "1") (pinfunction "P_1") (pintype "passive"))
      (node (ref "R3") (pin "1") (pinfunction "1_1") (pintype "passive"))
    )
    (net (code "60") (name "Net-(IC1-AFE1)") (class "Default")
      (node (ref "C49") (pin "2") (pinfunction "2_2") (pintype "passive"))
      (node (ref "IC1") (pin "33") (pinfunction "RCAL1_33") (pintype "bidirectional"))
      (node (ref "IC1") (pin "34") (pinfunction "AFE1_34") (pintype "bidirectional"))
      (node (ref "R9") (pin "1") (pinfunction "1_1") (pintype "passive"))
    )
    (net (code "61") (name "Net-(IC1-AFE2)") (class "Default")
      (node (ref "D4") (pin "A") (pinfunction "A_A") (pintype "passive"))
      (node (ref "IC1") (pin "35") (pinfunction "AFE2_35") (pintype "bidirectional"))
      (node (ref "R4") (pin "2") (pinfunction "2_2") (pintype "passive"))
    )
    (net (code "62") (name "Net-(IC1-AIN0)") (class "Default")
      (node (ref "IC1") (pin "39") (pinfunction "AIN0_39") (pintype "bidirectional"))
      (node (ref "R7") (pin "1") (pinfunction "1_1") (pintype "passive"))
    )
    (net (code "63") (name "Net-(IC1-AIN1)") (class "Default")
      (node (ref "IC1") (pin "38") (pinfunction "AIN1_38") (pintype "bidirectional"))
      (node (ref "R8") (pin "1") (pinfunction "1_1") (pintype "passive"))
    )
    (net (code "64") (name "Net-(IC1-AIN2)") (class "Default")
      (node (ref "IC1") (pin "37") (pinfunction "AIN2_37") (pintype "bidirectional"))
      (node (ref "R10") (pin "1") (pinfunction "1_1") (pintype "passive"))
    )
    (net (code "65") (name "Net-(IC1-AIN3{slash}BUF_VREF1V8)") (class "Default")
      (node (ref "IC1") (pin "36") (pinfunction "AIN3/BUF_VREF1V8_36") (pintype "bidirectional"))
      (node (ref "R11") (pin "1") (pinfunction "1_1") (pintype "passive"))
    )
    (net (code "66") (name "Net-(IC1-AIN4{slash}LPF0)") (class "Default")
      (node (ref "C50") (pin "2") (pinfunction "2_2") (pintype "passive"))
      (node (ref "IC1") (pin "32") (pinfunction "RCAL0_32") (pintype "bidirectional"))
      (node (ref "IC1") (pin "40") (pinfunction "AIN4/LPF0_40") (pintype "bidirectional"))
      (node (ref "R9") (pin "2") (pinfunction "2_2") (pintype "passive"))
    )
    (net (code "67") (name "Net-(IC1-AVDD_REG)") (class "Default")
      (node (ref "C9") (pin "1") (pinfunction "1_1") (pintype "passive"))
      (node (ref "IC1") (pin "5") (pinfunction "AVDD_REG_5") (pintype "bidirectional"))
    )
    (net (code "68") (name "Net-(IC1-CE0)") (class "Default")
      (node (ref "IC1") (pin "47") (pinfunction "CE0_47") (pintype "bidirectional"))
      (node (ref "R18") (pin "2") (pinfunction "2_2") (pintype "passive"))
    )
    (net (code "69") (name "Net-(IC1-CS)") (class "Default")
      (node (ref "IC1") (pin "15") (pinfunction "CS_15") (pintype "bidirectional"))
      (node (ref "IC3") (pin "14") (pinfunction "B2_14") (pintype "bidirectional"))
    )
    (net (code "70") (name "Net-(IC1-DE0)") (class "Default")
      (node (ref "D1") (pin "C") (pinfunction "C_C") (pintype "passive"))
      (node (ref "D2") (pin "A") (pinfunction "A_A") (pintype "passive"))
      (node (ref "IC1") (pin "46") (pinfunction "DE0_46") (pintype "bidirectional"))
      (node (ref "R3") (pin "2") (pinfunction "2_2") (pintype "passive"))
    )
    (net (code "71") (name "Net-(IC1-DVDD_REG_1V8)") (class "Default")
      (node (ref "C10") (pin "1") (pinfunction "1_1") (pintype "passive"))
      (node (ref "IC1") (pin "14") (pinfunction "DVDD_REG_1V8_14") (pintype "bidirectional"))
    )
    (net (code "72") (name "Net-(IC1-MISO)") (class "Default")
      (node (ref "IC1") (pin "18") (pinfunction "MISO_18") (pintype "bidirectional"))
      (node (ref "IC3") (pin "11") (pinfunction "B5_11") (pintype "bidirectional"))
    )
    (net (code "73") (name "Net-(IC1-MOSI)") (class "Default")
      (node (ref "IC1") (pin "17") (pinfunction "MOSI_17") (pintype "bidirectional"))
      (node (ref "IC3") (pin "12") (pinfunction "B4_12") (pintype "bidirectional"))
    )
    (net (code "74") (name "Net-(IC1-RE0)") (class "Default")
      (node (ref "IC1") (pin "48") (pinfunction "RE0_48") (pintype "bidirectional"))
      (node (ref "R16") (pin "2") (pinfunction "2_2") (pintype "passive"))
    )
    (net (code "75") (name "Net-(IC1-RESET)") (class "Default")
      (node (ref "IC1") (pin "22") (pinfunction "RESET_22") (pintype "bidirectional"))
      (node (ref "IC3") (pin "15") (pinfunction "B1_15") (pintype "bidirectional"))
    )
    (net (code "76") (name "Net-(IC1-SCLK)") (class "Default")
      (node (ref "IC1") (pin "16") (pinfunction "SCLK_16") (pintype "bidirectional"))
      (node (ref "IC3") (pin "13") (pinfunction "B3_13") (pintype "bidirectional"))
    )
    (net (code "77") (name "Net-(IC1-VBIAS0)") (class "Default")
      (node (ref "C11") (pin "1") (pinfunction "1_1") (pintype "passive"))
      (node (ref "IC1") (pin "8") (pinfunction "VBIAS0_8") (pintype "bidirectional"))
    )
    (net (code "78") (name "Net-(IC1-VBIAS_CAP)") (class "Default")
      (node (ref "C1") (pin "1") (pinfunction "1_1") (pintype "passive"))
      (node (ref "IC1") (pin "31") (pinfunction "VBIAS_CAP_31") (pintype "bidirectional"))
      (node (ref "R1") (pin "2") (pinfunction "2_2") (pintype "passive"))
      (node (ref "R12") (pin "2") (pinfunction "2_2") (pintype "passive"))
      (node (ref "R13") (pin "2") (pinfunction "2_2") (pintype "passive"))
      (node (ref "R2") (pin "2") (pinfunction "2_2") (pintype "passive"))
    )
    (net (code "79") (name "Net-(IC1-VREF_1V8)") (class "Default")
      (node (ref "C5") (pin "1") (pinfunction "1_1") (pintype "passive"))
      (node (ref "IC1") (pin "43") (pinfunction "VREF_1V8_43") (pintype "bidirectional"))
    )
    (net (code "80") (name "Net-(IC1-VREF_2V5)") (class "Default")
      (node (ref "C6") (pin "1") (pinfunction "1_1") (pintype "passive"))
      (node (ref "IC1") (pin "4") (pinfunction "VREF_2V5_4") (pintype "bidirectional"))
    )
    (net (code "81") (name "Net-(IC1-VZERO0)") (class "Default")
      (node (ref "C12") (pin "1") (pinfunction "1_1") (pintype "passive"))
      (node (ref "IC1") (pin "9") (pinfunction "VZERO0_9") (pintype "bidirectional"))
    )
    (net (code "82") (name "Net-(IC1-XTALI)") (class "Default")
      (node (ref "C13") (pin "1") (pinfunction "1_1") (pintype "passive"))
      (node (ref "IC1") (pin "11") (pinfunction "XTALI_11") (pintype "bidirectional"))
      (node (ref "Q1") (pin "1") (pinfunction "1_1") (pintype "passive"))
    )
    (net (code "83") (name "Net-(IC1-XTALO)") (class "Default")
      (node (ref "C16") (pin "1") (pinfunction "1_1") (pintype "passive"))
      (node (ref "IC1") (pin "12") (pinfunction "XTALO_12") (pintype "bidirectional"))
      (node (ref "Q1") (pin "3") (pinfunction "3_3") (pintype "passive"))
    )
    (net (code "84") (name "Net-(IC6A-NRST)") (class "Default")
      (node (ref "C25") (pin "1") (pinfunction "1_1") (pintype "passive"))
      (node (ref "IC6") (pin "14") (pinfunction "NRST_14") (pintype "bidirectional"))
      (node (ref "J1") (pin "3") (pinfunction "NRST_3") (pintype "power_in"))
      (node (ref "R29") (pin "2") (pinfunction "2_2") (pintype "passive"))
    )
    (net (code "85") (name "Net-(IC6A-OSC_IN)") (class "Default")
      (node (ref "C14") (pin "1") (pinfunction "1_1") (pintype "passive"))
      (node (ref "IC6") (pin "12") (pinfunction "OSC_IN_12") (pintype "bidirectional"))
      (node (ref "Q3") (pin "1") (pinfunction "1_1") (pintype "passive"))
    )
    (net (code "86") (name "Net-(IC6A-OSC_OUT)") (class "Default")
      (node (ref "C15") (pin "1") (pinfunction "1_1") (pintype "passive"))
      (node (ref "IC6") (pin "13") (pinfunction "OSC_OUT_13") (pintype "bidirectional"))
      (node (ref "Q3") (pin "3") (pinfunction "3_3") (pintype "passive"))
    )
    (net (code "87") (name "Net-(IC6A-PA9)") (class "Default")
      (node (ref "IC6") (pin "68") (pinfunction "PA9_68") (pintype "bidirectional"))
      (node (ref "UART") (pin "3") (pinfunction "3_3") (pintype "passive"))
    )
    (net (code "88") (name "Net-(IC6A-PA10)") (class "Default")
      (node (ref "IC6") (pin "69") (pinfunction "PA10_69") (pintype "bidirectional"))
      (node (ref "UART") (pin "1") (pinfunction "1_1") (pintype "passive"))
    )
    (net (code "89") (name "Net-(IC6A-PB8)") (class "Default")
      (node (ref "IC6") (pin "95") (pinfunction "PB8_95") (pintype "bidirectional"))
      (node (ref "Q2") (pin "1") (pinfunction "G_1") (pintype "passive"))
    )
    (net (code "90") (name "Net-(IC7-+IN)") (class "Default")
      (node (ref "C52") (pin "2") (pinfunction "2_2") (pintype "passive"))
      (node (ref "IC7") (pin "3") (pinfunction "+IN_3") (pintype "input"))
      (node (ref "R16") (pin "1") (pinfunction "1_1") (pintype "passive"))
    )
    (net (code "91") (name "Net-(IC7--IN)") (class "Default")
      (node (ref "C51") (pin "1") (pinfunction "1_1") (pintype "passive"))
      (node (ref "IC7") (pin "4") (pinfunction "-IN_4") (pintype "input"))
      (node (ref "R14") (pin "2") (pinfunction "2_2") (pintype "passive"))
      (node (ref "R15") (pin "2") (pinfunction "2_2") (pintype "passive"))
    )
    (net (code "92") (name "Net-(IC7-OUT)") (class "Default")
      (node (ref "C51") (pin "2") (pinfunction "2_2") (pintype "passive"))
      (node (ref "IC7") (pin "1") (pinfunction "OUT_1") (pintype "output"))
      (node (ref "R17") (pin "2") (pinfunction "2_2") (pintype "passive"))
    )
    (net (code "93") (name "Net-(JP1-Pad2)") (class "Default")
      (node (ref "JP1") (pin "2") (pinfunction "2_2") (pintype "passive"))
      (node (ref "X1") (pin "1") (pinfunction "1_1") (pintype "passive"))
    )
    (net (code "94") (name "Net-(L1-2)") (class "Default")
      (node (ref "C3") (pin "1") (pinfunction "1_1") (pintype "passive"))
      (node (ref "L1") (pin "P$2") (pinfunction "2_P$2") (pintype "passive"))
      (node (ref "V1") (pin "2") (pinfunction "+VIN_2") (pintype "passive"))
    )
    (net (code "95") (name "Net-(L2-1)") (class "Default")
      (node (ref "C7") (pin "1") (pinfunction "1_1") (pintype "passive"))
      (node (ref "L2") (pin "P$1") (pinfunction "1_P$1") (pintype "passive"))
      (node (ref "V1") (pin "4") (pinfunction "+VOUT_4") (pintype "passive"))
    )
    (net (code "96") (name "Net-(L2-2)") (class "Default")
      (node (ref "L2") (pin "P$2") (pinfunction "2_P$2") (pintype "passive"))
      (node (ref "L3") (pin "1") (pinfunction "1_1") (pintype "passive"))
    )
    (net (code "97") (name "Net-(L4-1)") (class "Default")
      (node (ref "C2") (pin "1") (pinfunction "1_1") (pintype "passive"))
      (node (ref "C7") (pin "2") (pinfunction "2_2") (pintype "passive"))
      (node (ref "L4") (pin "P$1") (pinfunction "1_P$1") (pintype "passive"))
      (node (ref "V1") (pin "3") (pinfunction "-VOUT_3") (pintype "passive"))
    )
    (net (code "98") (name "Net-(L4-2)") (class "Default")
      (node (ref "L4") (pin "P$2") (pinfunction "2_P$2") (pintype "passive"))
      (node (ref "L5") (pin "1") (pinfunction "1_1") (pintype "passive"))
    )
    (net (code "99") (name "Net-(Q2-D)") (class "Default")
      (node (ref "D5") (pin "A") (pinfunction "A_A") (pintype "passive"))
      (node (ref "Q2") (pin "3") (pinfunction "D_3") (pintype "passive"))
      (node (ref "SG1") (pin "-") (pinfunction "+_-") (pintype "passive"))
    )
    (net (code "100") (name "Net-(R21-Pad2)") (class "Default")
      (node (ref "R21") (pin "2") (pinfunction "2_2") (pintype "passive"))
      (node (ref "X1") (pin "2") (pinfunction "2_2") (pintype "passive"))
    )
    (net (code "101") (name "Net-(R22-Pad2)") (class "Default")
      (node (ref "R22") (pin "2") (pinfunction "2_2") (pintype "passive"))
      (node (ref "X1") (pin "3") (pinfunction "3_3") (pintype "passive"))
    )
    (net (code "102") (name "Net-(SG1--)") (class "Default")
      (node (ref "D5") (pin "C") (pinfunction "C_C") (pintype "passive"))
      (node (ref "R6") (pin "1") (pinfunction "1_1") (pintype "passive"))
      (node (ref "SG1") (pin "+") (pinfunction "-_+") (pintype "passive"))
    )
    (net (code "103") (name "Net-(U+-P)") (class "Default")
      (node (ref "C43") (pin "2") (pinfunction "2_2") (pintype "passive"))
      (node (ref "U+") (pin "1") (pinfunction "P_1") (pintype "passive"))
    )
    (net (code "104") (name "Net-(U--P)") (class "Default")
      (node (ref "C44") (pin "2") (pinfunction "2_2") (pintype "passive"))
      (node (ref "U-") (pin "1") (pinfunction "P_1") (pintype "passive"))
    )
    (net (code "105") (name "SD_CS") (class "Default")
      (node (ref "DISPLAY") (pin "36") (pinfunction "CS_36") (pintype "bidirectional"))
      (node (ref "IC6") (pin "26") (pinfunction "PA3_26") (pintype "bidirectional"))
    )
    (net (code "106") (name "SWCLK") (class "Default")
      (node (ref "IC6") (pin "76") (pinfunction "PA14_76") (pintype "bidirectional"))
      (node (ref "J1") (pin "4") (pinfunction "SWCLK_4") (pintype "bidirectional"))
    )
    (net (code "107") (name "SWDIO") (class "Default")
      (node (ref "IC6") (pin "72") (pinfunction "PA13_72") (pintype "bidirectional"))
      (node (ref "J1") (pin "2") (pinfunction "SDWIO_2") (pintype "power_in"))
    )
    (net (code "108") (name "TFT_CS") (class "Default")
      (node (ref "DISPLAY") (pin "29") (pinfunction "CS_29") (pintype "bidirectional"))
      (node (ref "IC6") (pin "24") (pinfunction "PA1_24") (pintype "bidirectional"))
    )
    (net (code "109") (name "TFT_RD") (class "Default")
      (node (ref "DISPLAY") (pin "11") (pinfunction "RD_11") (pintype "bidirectional"))
      (node (ref "IC6") (pin "9") (pinfunction "PC15_9") (pintype "bidirectional"))
    )
    (net (code "110") (name "TFT_RS") (class "Default")
      (node (ref "DISPLAY") (pin "7") (pinfunction "RS_7") (pintype "bidirectional"))
      (node (ref "IC6") (pin "7") (pinfunction "PC13_7") (pintype "bidirectional"))
    )
    (net (code "111") (name "TFT_RST") (class "Default")
      (node (ref "DISPLAY") (pin "33") (pinfunction "RST_33") (pintype "bidirectional"))
      (node (ref "IC6") (pin "25") (pinfunction "PA2_25") (pintype "bidirectional"))
    )
    (net (code "112") (name "TFT_WR") (class "Default")
      (node (ref "DISPLAY") (pin "9") (pinfunction "WR_9") (pintype "bidirectional"))
      (node (ref "IC6") (pin "8") (pinfunction "PC14_8") (pintype "bidirectional"))
    )
    (net (code "113") (name "TOUCH_CS") (class "Default")
      (node (ref "DISPLAY") (pin "20") (pinfunction "CS_20") (pintype "bidirectional"))
      (node (ref "IC6") (pin "10") (pinfunction "PF9_10") (pintype "bidirectional"))
    )
    (net (code "114") (name "TOUCH_IRQ") (class "Default")
      (node (ref "DISPLAY") (pin "28") (pinfunction "IRQ_28") (pintype "bidirectional"))
      (node (ref "IC6") (pin "23") (pinfunction "PA0-WKUP_23") (pintype "bidirectional"))
    )
    (net (code "115") (name "USB_IDENT") (class "Default")
      (node (ref "IC6") (pin "67") (pinfunction "PA8_67") (pintype "bidirectional"))
      (node (ref "R5") (pin "2") (pinfunction "2_2") (pintype "passive"))
    )
    (net (code "116") (name "USB_N") (class "Default")
      (node (ref "IC6") (pin "70") (pinfunction "PA11_70") (pintype "bidirectional"))
      (node (ref "R21") (pin "1") (pinfunction "1_1") (pintype "passive"))
    )
    (net (code "117") (name "USB_P") (class "Default")
      (node (ref "IC6") (pin "71") (pinfunction "PA12_71") (pintype "bidirectional"))
      (node (ref "R22") (pin "1") (pinfunction "1_1") (pintype "passive"))
      (node (ref "R5") (pin "1") (pinfunction "1_1") (pintype "passive"))
    )
    (net (code "118") (name "VCC") (class "Default")
      (node (ref "C17") (pin "1") (pinfunction "1_1") (pintype "passive"))
      (node (ref "C18") (pin "1") (pinfunction "1_1") (pintype "passive"))
      (node (ref "C27") (pin "1") (pinfunction "1_1") (pintype "passive"))
      (node (ref "C34") (pin "1") (pinfunction "1_1") (pintype "passive"))
      (node (ref "IC1") (pin "26") (pinfunction "IOVDD_26") (pintype "bidirectional"))
      (node (ref "IC1") (pin "6") (pinfunction "DVDD_6") (pintype "bidirectional"))
      (node (ref "IC2") (pin "2") (pinfunction "VOUT_2") (pintype "power_in"))
      (node (ref "IC2") (pin "4") (pinfunction "VOUT_4") (pintype "power_in"))
      (node (ref "IC3") (pin "10") (pinfunction "EN2_10") (pintype "bidirectional"))
      (node (ref "IC3") (pin "16") (pinfunction "VDD2_16") (pintype "bidirectional"))
      (node (ref "L9") (pin "1") (pinfunction "1_1") (pintype "passive"))
    )
    (net (code "119") (name "unconnected-(DISPLAYA-BUSY-Pad24)") (class "Default")
      (node (ref "DISPLAY") (pin "24") (pinfunction "BUSY_24") (pintype "bidirectional"))
    )
    (net (code "120") (name "unconnected-(IC1-AFE3-Pad27)") (class "Default")
      (node (ref "IC1") (pin "27") (pinfunction "AFE3_27") (pintype "bidirectional"))
    )
    (net (code "121") (name "unconnected-(IC1-AFE4-Pad28)") (class "Default")
      (node (ref "IC1") (pin "28") (pinfunction "AFE4_28") (pintype "bidirectional"))
    )
    (net (code "122") (name "unconnected-(IC1-GPIO0-Pad19)") (class "Default")
      (node (ref "IC1") (pin "19") (pinfunction "GPIO0_19") (pintype "bidirectional"))
    )
    (net (code "123") (name "unconnected-(IC1-GPIO1-Pad20)") (class "Default")
      (node (ref "IC1") (pin "20") (pinfunction "GPIO1_20") (pintype "bidirectional"))
    )
    (net (code "124") (name "unconnected-(IC1-GPIO2-Pad21)") (class "Default")
      (node (ref "IC1") (pin "21") (pinfunction "GPIO2_21") (pintype "bidirectional"))
    )
    (net (code "125") (name "unconnected-(IC1-RC0_0-Pad3)") (class "Default")
      (node (ref "IC1") (pin "3") (pinfunction "RC0_0_3") (pintype "bidirectional"))
    )
    (net (code "126") (name "unconnected-(IC1-RC0_1-Pad2)") (class "Default")
      (node (ref "IC1") (pin "2") (pinfunction "RC0_1_2") (pintype "bidirectional"))
    )
    (net (code "127") (name "unconnected-(IC1-RC0_2-Pad1)") (class "Default")
      (node (ref "IC1") (pin "1") (pinfunction "RC0_2_1") (pintype "bidirectional"))
    )
    (net (code "128") (name "unconnected-(IC1-SE0-Pad45)") (class "Default")
      (node (ref "IC1") (pin "45") (pinfunction "SE0_45") (pintype "bidirectional"))
    )
    (net (code "129") (name "unconnected-(IC6A-PA4-Pad29)") (class "Default")
      (node (ref "IC6") (pin "29") (pinfunction "PA4_29") (pintype "bidirectional"))
    )
    (net (code "130") (name "unconnected-(IC6A-PA15-Pad77)") (class "Default")
      (node (ref "IC6") (pin "77") (pinfunction "PA15_77") (pintype "bidirectional"))
    )
    (net (code "131") (name "unconnected-(IC6A-PB0-Pad35)") (class "Default")
      (node (ref "IC6") (pin "35") (pinfunction "PB0_35") (pintype "bidirectional"))
    )
    (net (code "132") (name "unconnected-(IC6A-PB9-Pad96)") (class "Default")
      (node (ref "IC6") (pin "96") (pinfunction "PB9_96") (pintype "bidirectional"))
    )
    (net (code "133") (name "unconnected-(IC6A-PC0-Pad15)") (class "Default")
      (node (ref "IC6") (pin "15") (pinfunction "PC0_15") (pintype "bidirectional"))
    )
    (net (code "134") (name "unconnected-(IC6A-PC1-Pad16)") (class "Default")
      (node (ref "IC6") (pin "16") (pinfunction "PC1_16") (pintype "bidirectional"))
    )
    (net (code "135") (name "unconnected-(IC6A-PC2-Pad17)") (class "Default")
      (node (ref "IC6") (pin "17") (pinfunction "PC2_17") (pintype "bidirectional"))
    )
    (net (code "136") (name "unconnected-(IC6A-PC3-Pad18)") (class "Default")
      (node (ref "IC6") (pin "18") (pinfunction "PC3_18") (pintype "bidirectional"))
    )
    (net (code "137") (name "unconnected-(IC6A-PC4-Pad33)") (class "Default")
      (node (ref "IC6") (pin "33") (pinfunction "PC4_33") (pintype "bidirectional"))
    )
    (net (code "138") (name "unconnected-(IC6A-PC5-Pad34)") (class "Default")
      (node (ref "IC6") (pin "34") (pinfunction "PC5_34") (pintype "bidirectional"))
    )
    (net (code "139") (name "unconnected-(IC6A-PC10-Pad78)") (class "Default")
      (node (ref "IC6") (pin "78") (pinfunction "PC10_78") (pintype "bidirectional"))
    )
    (net (code "140") (name "unconnected-(IC6A-PC11-Pad79)") (class "Default")
      (node (ref "IC6") (pin "79") (pinfunction "PC11_79") (pintype "bidirectional"))
    )
    (net (code "141") (name "unconnected-(IC6A-PC12-Pad80)") (class "Default")
      (node (ref "IC6") (pin "80") (pinfunction "PC12_80") (pintype "bidirectional"))
    )
    (net (code "142") (name "unconnected-(IC6A-PD0-Pad81)") (class "Default")
      (node (ref "IC6") (pin "81") (pinfunction "PD0_81") (pintype "bidirectional"))
    )
    (net (code "143") (name "unconnected-(IC6A-PD1-Pad82)") (class "Default")
      (node (ref "IC6") (pin "82") (pinfunction "PD1_82") (pintype "bidirectional"))
    )
    (net (code "144") (name "unconnected-(IC6A-PD2-Pad83)") (class "Default")
      (node (ref "IC6") (pin "83") (pinfunction "PD2_83") (pintype "bidirectional"))
    )
    (net (code "145") (name "unconnected-(IC6A-PD3-Pad84)") (class "Default")
      (node (ref "IC6") (pin "84") (pinfunction "PD3_84") (pintype "bidirectional"))
    )
    (net (code "146") (name "unconnected-(IC6A-PD4-Pad85)") (class "Default")
      (node (ref "IC6") (pin "85") (pinfunction "PD4_85") (pintype "bidirectional"))
    )
    (net (code "147") (name "unconnected-(IC6A-PD5-Pad86)") (class "Default")
      (node (ref "IC6") (pin "86") (pinfunction "PD5_86") (pintype "bidirectional"))
    )
    (net (code "148") (name "unconnected-(IC6A-PD6-Pad87)") (class "Default")
      (node (ref "IC6") (pin "87") (pinfunction "PD6_87") (pintype "bidirectional"))
    )
    (net (code "149") (name "unconnected-(IC6A-PD7-Pad88)") (class "Default")
      (node (ref "IC6") (pin "88") (pinfunction "PD7_88") (pintype "bidirectional"))
    )
    (net (code "150") (name "unconnected-(IC6A-PF2-Pad19)") (class "Default")
      (node (ref "IC6") (pin "19") (pinfunction "PF2_19") (pintype "bidirectional"))
    )
    (net (code "151") (name "unconnected-(IC6A-PF4-Pad27)") (class "Default")
      (node (ref "IC6") (pin "27") (pinfunction "PF4_27") (pintype "bidirectional"))
    )
    (net (code "152") (name "unconnected-(IC6A-PF6-Pad73)") (class "Default")
      (node (ref "IC6") (pin "73") (pinfunction "PF6_73") (pintype "bidirectional"))
    )
    (net (code "153") (name "unconnected-(IC6A-PF10-Pad11)") (class "Default")
      (node (ref "IC6") (pin "11") (pinfunction "PF10_11") (pintype "bidirectional"))
    )
    (net (code "154") (name "unconnected-(J1-SWO-Pad6)") (class "Default")
      (node (ref "J1") (pin "6") (pinfunction "SWO_6") (pintype "bidirectional"))
    )
  )
)
